# 05_LMS7002M_Misc.net
KiCad netlist of a schematic drawn in Altium Designer
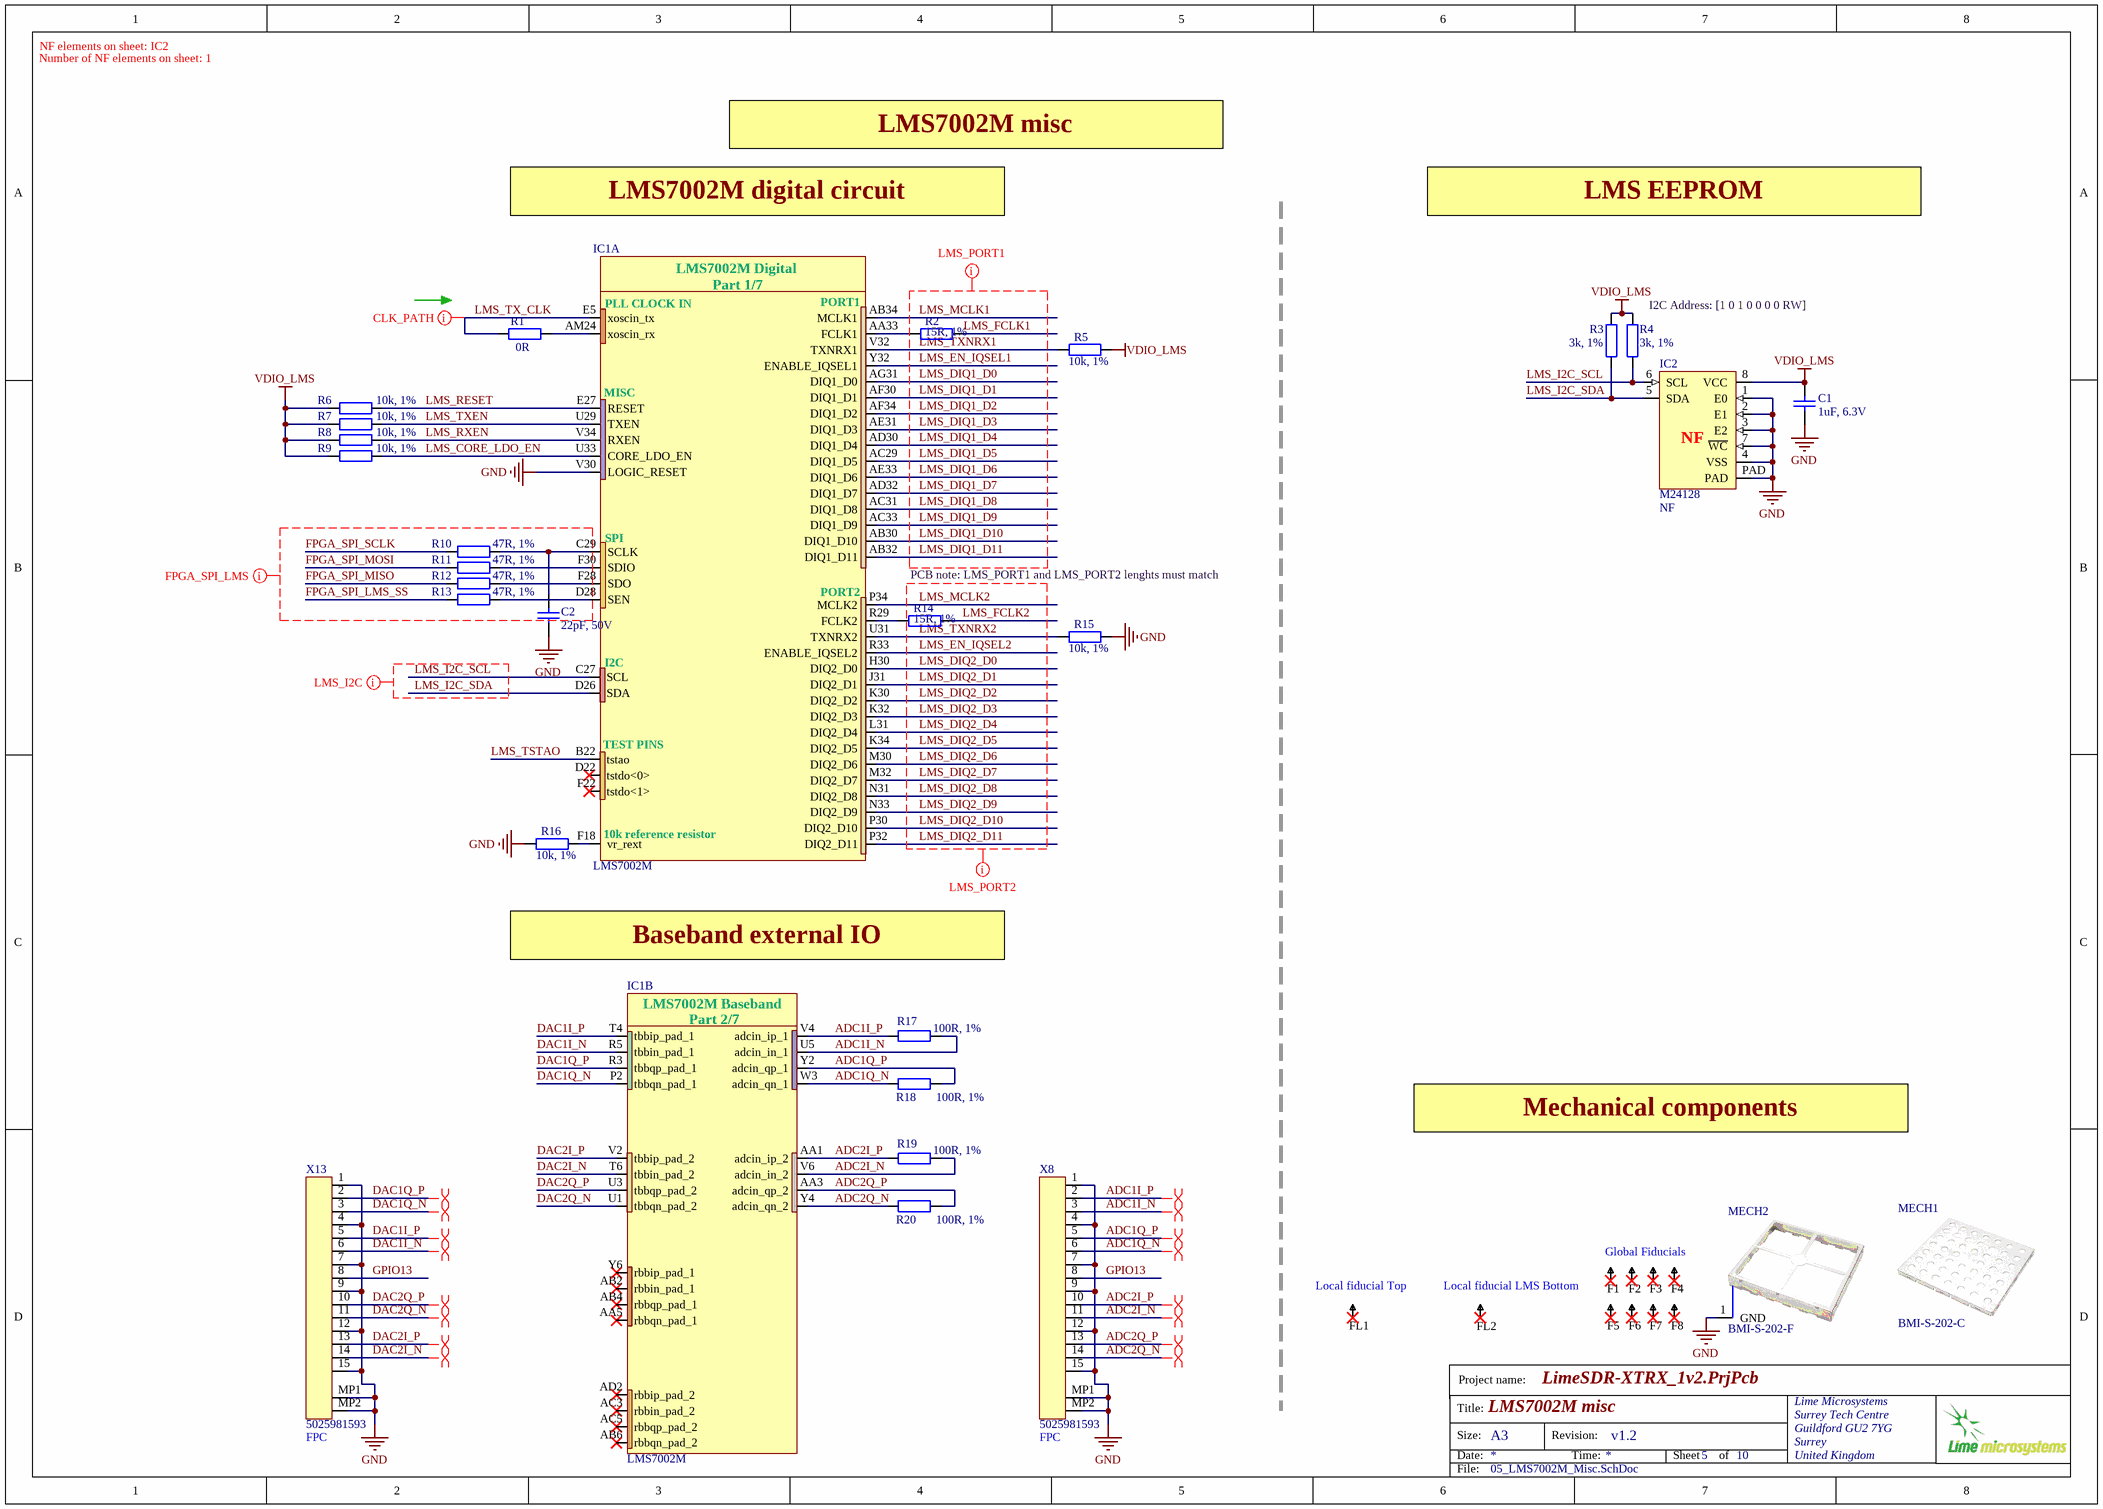
[diagram p0: 05_LMS7002M_Misc.SchDoc]

(export (version "E")
  (design (tool "Eeschema 10.0.6"))
  (components
    (comp (ref "C1")
      (value "1uF, 6.3V")
      (footprint "CAP0201")
      (fields (field (name "TOLERANCE") "±20%") (field (name "MANUFACTURER") "TDK Corporation"))
      (libsource (lib "LimeMicroAltiumLib_schLib") (part "Cap_0402"))
    )
    (comp (ref "C2")
      (value "22pF, 50V")
      (footprint "CAP0201")
      (fields
        (field (name "MANUFACTURER") "Murata")
        (field (name "TOLERANCE") "5%")
        (field (name "VOLTAGE") "50V")
      )
      (libsource (lib "LimeMicroAltiumLib_schLib") (part "Cap_0402"))
    )
    (comp (ref "F1")
      (value "Fiducial")
      (footprint "Fiducial")
      (libsource (lib "VGTU_Altium_lib") (part "Fiducial"))
    )
    (comp (ref "F2")
      (value "Fiducial")
      (footprint "Fiducial")
      (libsource (lib "VGTU_Altium_lib") (part "Fiducial"))
    )
    (comp (ref "F3")
      (value "Fiducial")
      (footprint "Fiducial")
      (libsource (lib "VGTU_Altium_lib") (part "Fiducial"))
    )
    (comp (ref "F4")
      (value "Fiducial")
      (footprint "Fiducial")
      (libsource (lib "VGTU_Altium_lib") (part "Fiducial"))
    )
    (comp (ref "F5")
      (value "Fiducial")
      (footprint "Fiducial")
      (libsource (lib "VGTU_Altium_lib") (part "Fiducial"))
    )
    (comp (ref "F6")
      (value "Fiducial")
      (footprint "Fiducial")
      (libsource (lib "VGTU_Altium_lib") (part "Fiducial"))
    )
    (comp (ref "F7")
      (value "Fiducial")
      (footprint "Fiducial")
      (libsource (lib "VGTU_Altium_lib") (part "Fiducial"))
    )
    (comp (ref "F8")
      (value "Fiducial")
      (footprint "Fiducial")
      (libsource (lib "VGTU_Altium_lib") (part "Fiducial"))
    )
    (comp (ref "FL1")
      (value "Fiducial")
      (footprint "Fiducial_local")
      (libsource (lib "") (part "Fiducial_1"))
    )
    (comp (ref "FL2")
      (value "Fiducial")
      (footprint "Fiducial_local")
      (libsource (lib "") (part "Fiducial_1"))
    )
    (comp (ref "IC1")
      (value "LMS7002M")
      (footprint "LMS7002M_v5_LESS_SILK")
      (description "Schematic symbol revision 4. Default footprint - 0.31mm pad")
      (fields (field (name "MANUFACTURER") "Lime Microsystems"))
      (libsource (lib "LimeMicroAltiumLib_schLib_r04") (part "LMS7002Mr4"))
    )
    (comp (ref "IC2")
      (value "M24128")
      (footprint "M24128-DFMC6TG")
      (fields (field (name "MANUFACTURER") "STMicroelectronics") (field (name "ASSEMBLY INFO") "NF"))
      (libsource (lib "LimeMicroAltiumLib_schLib") (part "M24128-DFMC6TG"))
    )
    (comp (ref "MECH1")
      (value "BMI-S-202-C")
      (footprint "BMI-S-202-C_RF_SHIELD_COVER")
      (fields (field (name "MANUFACTURER") "Laird"))
      (libsource (lib "LimeMicroAltiumLib_schLib_r04") (part "RFI_SHIELD_COVER_BMI-S-202-C"))
    )
    (comp (ref "MECH2")
      (value "BMI-S-202-F")
      (footprint "BMI-S-202-F_RF_SHIELD_FRAME_v3")
      (fields (field (name "MANUFACTURER") "Laird"))
      (libsource (lib "LimeMicroAltiumLib_schLib_r04") (part "RFI_SHIELD_FRAME_BMI-S-202-F"))
    )
    (comp (ref "R1")
      (value "0R")
      (footprint "RES0201")
      (fields (field (name "MANUFACTURER") "Yageo") (field (name "TOLERANCE") "5%"))
      (libsource (lib "LimeFPGAboard_schLib") (part "Res_0402"))
    )
    (comp (ref "R2")
      (value "15R, 1%")
      (footprint "RES0201")
      (fields (field (name "MANUFACTURER") "Yageo") (field (name "TOLERANCE") "1%"))
      (libsource (lib "LimeFPGAboard_schLib") (part "Res_0402"))
    )
    (comp (ref "R3")
      (value "3k, 1%")
      (footprint "RES0201")
      (fields (field (name "MANUFACTURER") "Yageo") (field (name "TOLERANCE") "1%"))
      (libsource (lib "LimeFPGAboard_schLib") (part "Res_0402"))
    )
    (comp (ref "R4")
      (value "3k, 1%")
      (footprint "RES0201")
      (fields (field (name "MANUFACTURER") "Yageo") (field (name "TOLERANCE") "1%"))
      (libsource (lib "LimeFPGAboard_schLib") (part "Res_0402"))
    )
    (comp (ref "R5")
      (value "10k, 1%")
      (footprint "RES0201")
      (fields (field (name "MANUFACTURER") "Yageo") (field (name "TOLERANCE") "1%"))
      (libsource (lib "LimeFPGAboard_schLib") (part "Res_0402"))
    )
    (comp (ref "R6")
      (value "10k, 1%")
      (footprint "RES0201")
      (fields (field (name "MANUFACTURER") "Yageo") (field (name "TOLERANCE") "1%"))
      (libsource (lib "LimeFPGAboard_schLib") (part "Res_0402"))
    )
    (comp (ref "R7")
      (value "10k, 1%")
      (footprint "RES0201")
      (fields (field (name "MANUFACTURER") "Yageo") (field (name "TOLERANCE") "1%"))
      (libsource (lib "LimeFPGAboard_schLib") (part "Res_0402"))
    )
    (comp (ref "R8")
      (value "10k, 1%")
      (footprint "RES0201")
      (fields (field (name "MANUFACTURER") "Yageo") (field (name "TOLERANCE") "1%"))
      (libsource (lib "LimeFPGAboard_schLib") (part "Res_0402"))
    )
    (comp (ref "R9")
      (value "10k, 1%")
      (footprint "RES0201")
      (fields (field (name "MANUFACTURER") "Yageo") (field (name "TOLERANCE") "1%"))
      (libsource (lib "LimeFPGAboard_schLib") (part "Res_0402"))
    )
    (comp (ref "R10")
      (value "47R, 1%")
      (footprint "RES0201")
      (fields (field (name "MANUFACTURER") "Yageo") (field (name "TOLERANCE") "1%"))
      (libsource (lib "LimeFPGAboard_schLib") (part "Res_0402"))
    )
    (comp (ref "R11")
      (value "47R, 1%")
      (footprint "RES0201")
      (fields (field (name "MANUFACTURER") "Yageo") (field (name "TOLERANCE") "1%"))
      (libsource (lib "LimeFPGAboard_schLib") (part "Res_0402"))
    )
    (comp (ref "R12")
      (value "47R, 1%")
      (footprint "RES0201")
      (fields (field (name "MANUFACTURER") "Yageo") (field (name "TOLERANCE") "1%"))
      (libsource (lib "LimeFPGAboard_schLib") (part "Res_0402"))
    )
    (comp (ref "R13")
      (value "47R, 1%")
      (footprint "RES0201")
      (fields (field (name "MANUFACTURER") "Yageo") (field (name "TOLERANCE") "1%"))
      (libsource (lib "LimeFPGAboard_schLib") (part "Res_0402"))
    )
    (comp (ref "R14")
      (value "15R, 1%")
      (footprint "RES0201")
      (fields (field (name "MANUFACTURER") "Yageo") (field (name "TOLERANCE") "1%"))
      (libsource (lib "LimeFPGAboard_schLib") (part "Res_0402"))
    )
    (comp (ref "R15")
      (value "10k, 1%")
      (footprint "RES0201")
      (fields (field (name "MANUFACTURER") "Yageo") (field (name "TOLERANCE") "1%"))
      (libsource (lib "LimeFPGAboard_schLib") (part "Res_0402"))
    )
    (comp (ref "R16")
      (value "10k, 1%")
      (footprint "RES0201")
      (fields (field (name "MANUFACTURER") "Yageo") (field (name "TOLERANCE") "1%"))
      (libsource (lib "LimeFPGAboard_schLib") (part "Res_0402"))
    )
    (comp (ref "R17")
      (value "100R, 1%")
      (footprint "RES0201")
      (fields (field (name "MANUFACTURER") "Yageo") (field (name "TOLERANCE") "1%"))
      (libsource (lib "LimeFPGAboard_schLib") (part "Res_0402"))
    )
    (comp (ref "R18")
      (value "100R, 1%")
      (footprint "RES0201")
      (fields (field (name "MANUFACTURER") "Yageo") (field (name "TOLERANCE") "1%"))
      (libsource (lib "LimeFPGAboard_schLib") (part "Res_0402"))
    )
    (comp (ref "R19")
      (value "100R, 1%")
      (footprint "RES0201")
      (fields (field (name "MANUFACTURER") "Yageo") (field (name "TOLERANCE") "1%"))
      (libsource (lib "LimeFPGAboard_schLib") (part "Res_0402"))
    )
    (comp (ref "R20")
      (value "100R, 1%")
      (footprint "RES0201")
      (fields (field (name "MANUFACTURER") "Yageo") (field (name "TOLERANCE") "1%"))
      (libsource (lib "LimeFPGAboard_schLib") (part "Res_0402"))
    )
    (comp (ref "X8")
      (value "5025981593")
      (footprint "5025981593_FPC_connector")
      (fields (field (name "MANUFACTURER") "Molex"))
      (libsource (lib "LimeMicroAltiumLib_schLib_r04") (part "5025981593_FPC_connector"))
    )
    (comp (ref "X13")
      (value "5025981593")
      (footprint "5025981593_FPC_connector")
      (fields (field (name "MANUFACTURER") "Molex"))
      (libsource (lib "LimeMicroAltiumLib_schLib_r04") (part "5025981593_FPC_connector"))
    )
  )
  (nets
    (net (code "1") (name "/ADC1I_N") (class "Default")
      (node (ref "IC1") (pin "U5") (pinfunction "adcin_in_1_U5") (pintype "passive"))
      (node (ref "R17") (pin "2") (pinfunction "2_2") (pintype "passive"))
      (node (ref "X8") (pin "3") (pinfunction "3_3") (pintype "passive"))
    )
    (net (code "2") (name "/ADC1I_P") (class "Default")
      (node (ref "IC1") (pin "V4") (pinfunction "adcin_ip_1_V4") (pintype "passive"))
      (node (ref "R17") (pin "1") (pinfunction "1_1") (pintype "passive"))
      (node (ref "X8") (pin "2") (pinfunction "2_2") (pintype "passive"))
    )
    (net (code "3") (name "/ADC1Q_N") (class "Default")
      (node (ref "IC1") (pin "W3") (pinfunction "adcin_qn_1_W3") (pintype "passive"))
      (node (ref "R18") (pin "1") (pinfunction "1_1") (pintype "passive"))
      (node (ref "X8") (pin "6") (pinfunction "6_6") (pintype "passive"))
    )
    (net (code "4") (name "/ADC1Q_P") (class "Default")
      (node (ref "IC1") (pin "Y2") (pinfunction "adcin_qp_1_Y2") (pintype "passive"))
      (node (ref "R18") (pin "2") (pinfunction "2_2") (pintype "passive"))
      (node (ref "X8") (pin "5") (pinfunction "5_5") (pintype "passive"))
    )
    (net (code "5") (name "/ADC2I_N") (class "Default")
      (node (ref "IC1") (pin "V6") (pinfunction "adcin_in_2_V6") (pintype "passive"))
      (node (ref "R19") (pin "2") (pinfunction "2_2") (pintype "passive"))
      (node (ref "X8") (pin "11") (pinfunction "11_11") (pintype "passive"))
    )
    (net (code "6") (name "/ADC2I_P") (class "Default")
      (node (ref "IC1") (pin "AA1") (pinfunction "adcin_ip_2_AA1") (pintype "passive"))
      (node (ref "R19") (pin "1") (pinfunction "1_1") (pintype "passive"))
      (node (ref "X8") (pin "10") (pinfunction "10_10") (pintype "passive"))
    )
    (net (code "7") (name "/ADC2Q_N") (class "Default")
      (node (ref "IC1") (pin "Y4") (pinfunction "adcin_qn_2_Y4") (pintype "passive"))
      (node (ref "R20") (pin "1") (pinfunction "1_1") (pintype "passive"))
      (node (ref "X8") (pin "14") (pinfunction "14_14") (pintype "passive"))
    )
    (net (code "8") (name "/ADC2Q_P") (class "Default")
      (node (ref "IC1") (pin "AA3") (pinfunction "adcin_qp_2_AA3") (pintype "passive"))
      (node (ref "R20") (pin "2") (pinfunction "2_2") (pintype "passive"))
      (node (ref "X8") (pin "13") (pinfunction "13_13") (pintype "passive"))
    )
    (net (code "9") (name "/DAC1I_N") (class "Default")
      (node (ref "IC1") (pin "R5") (pinfunction "tbbin_pad_1_R5") (pintype "passive"))
      (node (ref "X13") (pin "6") (pinfunction "6_6") (pintype "passive"))
    )
    (net (code "10") (name "/DAC1I_P") (class "Default")
      (node (ref "IC1") (pin "T4") (pinfunction "tbbip_pad_1_T4") (pintype "passive"))
      (node (ref "X13") (pin "5") (pinfunction "5_5") (pintype "passive"))
    )
    (net (code "11") (name "/DAC1Q_N") (class "Default")
      (node (ref "IC1") (pin "P2") (pinfunction "tbbqn_pad_1_P2") (pintype "passive"))
      (node (ref "X13") (pin "3") (pinfunction "3_3") (pintype "passive"))
    )
    (net (code "12") (name "/DAC1Q_P") (class "Default")
      (node (ref "IC1") (pin "R3") (pinfunction "tbbqp_pad_1_R3") (pintype "passive"))
      (node (ref "X13") (pin "2") (pinfunction "2_2") (pintype "passive"))
    )
    (net (code "13") (name "/DAC2I_N") (class "Default")
      (node (ref "IC1") (pin "T6") (pinfunction "tbbin_pad_2_T6") (pintype "passive"))
      (node (ref "X13") (pin "14") (pinfunction "14_14") (pintype "passive"))
    )
    (net (code "14") (name "/DAC2I_P") (class "Default")
      (node (ref "IC1") (pin "V2") (pinfunction "tbbip_pad_2_V2") (pintype "passive"))
      (node (ref "X13") (pin "13") (pinfunction "13_13") (pintype "passive"))
    )
    (net (code "15") (name "/DAC2Q_N") (class "Default")
      (node (ref "IC1") (pin "U1") (pinfunction "tbbqn_pad_2_U1") (pintype "passive"))
      (node (ref "X13") (pin "11") (pinfunction "11_11") (pintype "passive"))
    )
    (net (code "16") (name "/DAC2Q_P") (class "Default")
      (node (ref "IC1") (pin "U3") (pinfunction "tbbqp_pad_2_U3") (pintype "passive"))
      (node (ref "X13") (pin "10") (pinfunction "10_10") (pintype "passive"))
    )
    (net (code "17") (name "/FPGA_SPI_LMS_SS") (class "Default")
      (node (ref "R13") (pin "2") (pinfunction "2_2") (pintype "passive"))
    )
    (net (code "18") (name "/FPGA_SPI_MISO") (class "Default")
      (node (ref "R12") (pin "2") (pinfunction "2_2") (pintype "passive"))
    )
    (net (code "19") (name "/FPGA_SPI_MOSI") (class "Default")
      (node (ref "R11") (pin "2") (pinfunction "2_2") (pintype "passive"))
    )
    (net (code "20") (name "/FPGA_SPI_SCLK") (class "Default")
      (node (ref "R10") (pin "2") (pinfunction "2_2") (pintype "passive"))
    )
    (net (code "21") (name "/GPIO13") (class "Default")
      (node (ref "X13") (pin "8") (pinfunction "8_8") (pintype "passive"))
      (node (ref "X8") (pin "8") (pinfunction "8_8") (pintype "passive"))
    )
    (net (code "22") (name "/LMS_CORE_LDO_EN") (class "Default")
      (node (ref "IC1") (pin "U33") (pinfunction "CORE_LDO_EN_U33") (pintype "passive"))
      (node (ref "R9") (pin "1") (pinfunction "1_1") (pintype "passive"))
    )
    (net (code "23") (name "/LMS_DIQ1_D0") (class "Default")
      (node (ref "IC1") (pin "AG31") (pinfunction "DIQ1_D0_AG31") (pintype "passive"))
    )
    (net (code "24") (name "/LMS_DIQ1_D1") (class "Default")
      (node (ref "IC1") (pin "AF30") (pinfunction "DIQ1_D1_AF30") (pintype "passive"))
    )
    (net (code "25") (name "/LMS_DIQ1_D2") (class "Default")
      (node (ref "IC1") (pin "AF34") (pinfunction "DIQ1_D2_AF34") (pintype "passive"))
    )
    (net (code "26") (name "/LMS_DIQ1_D3") (class "Default")
      (node (ref "IC1") (pin "AE31") (pinfunction "DIQ1_D3_AE31") (pintype "passive"))
    )
    (net (code "27") (name "/LMS_DIQ1_D4") (class "Default")
      (node (ref "IC1") (pin "AD30") (pinfunction "DIQ1_D4_AD30") (pintype "passive"))
    )
    (net (code "28") (name "/LMS_DIQ1_D5") (class "Default")
      (node (ref "IC1") (pin "AC29") (pinfunction "DIQ1_D5_AC29") (pintype "passive"))
    )
    (net (code "29") (name "/LMS_DIQ1_D6") (class "Default")
      (node (ref "IC1") (pin "AE33") (pinfunction "DIQ1_D6_AE33") (pintype "passive"))
    )
    (net (code "30") (name "/LMS_DIQ1_D7") (class "Default")
      (node (ref "IC1") (pin "AD32") (pinfunction "DIQ1_D7_AD32") (pintype "passive"))
    )
    (net (code "31") (name "/LMS_DIQ1_D8") (class "Default")
      (node (ref "IC1") (pin "AC31") (pinfunction "DIQ1_D8_AC31") (pintype "passive"))
    )
    (net (code "32") (name "/LMS_DIQ1_D9") (class "Default")
      (node (ref "IC1") (pin "AC33") (pinfunction "DIQ1_D9_AC33") (pintype "passive"))
    )
    (net (code "33") (name "/LMS_DIQ1_D10") (class "Default")
      (node (ref "IC1") (pin "AB30") (pinfunction "DIQ1_D10_AB30") (pintype "passive"))
    )
    (net (code "34") (name "/LMS_DIQ1_D11") (class "Default")
      (node (ref "IC1") (pin "AB32") (pinfunction "DIQ1_D11_AB32") (pintype "passive"))
    )
    (net (code "35") (name "/LMS_DIQ2_D0") (class "Default")
      (node (ref "IC1") (pin "H30") (pinfunction "DIQ2_D0_H30") (pintype "passive"))
    )
    (net (code "36") (name "/LMS_DIQ2_D1") (class "Default")
      (node (ref "IC1") (pin "J31") (pinfunction "DIQ2_D1_J31") (pintype "passive"))
    )
    (net (code "37") (name "/LMS_DIQ2_D2") (class "Default")
      (node (ref "IC1") (pin "K30") (pinfunction "DIQ2_D2_K30") (pintype "passive"))
    )
    (net (code "38") (name "/LMS_DIQ2_D3") (class "Default")
      (node (ref "IC1") (pin "K32") (pinfunction "DIQ2_D3_K32") (pintype "passive"))
    )
    (net (code "39") (name "/LMS_DIQ2_D4") (class "Default")
      (node (ref "IC1") (pin "L31") (pinfunction "DIQ2_D4_L31") (pintype "passive"))
    )
    (net (code "40") (name "/LMS_DIQ2_D5") (class "Default")
      (node (ref "IC1") (pin "K34") (pinfunction "DIQ2_D5_K34") (pintype "passive"))
    )
    (net (code "41") (name "/LMS_DIQ2_D6") (class "Default")
      (node (ref "IC1") (pin "M30") (pinfunction "DIQ2_D6_M30") (pintype "passive"))
    )
    (net (code "42") (name "/LMS_DIQ2_D7") (class "Default")
      (node (ref "IC1") (pin "M32") (pinfunction "DIQ2_D7_M32") (pintype "passive"))
    )
    (net (code "43") (name "/LMS_DIQ2_D8") (class "Default")
      (node (ref "IC1") (pin "N31") (pinfunction "DIQ2_D8_N31") (pintype "passive"))
    )
    (net (code "44") (name "/LMS_DIQ2_D9") (class "Default")
      (node (ref "IC1") (pin "N33") (pinfunction "DIQ2_D9_N33") (pintype "passive"))
    )
    (net (code "45") (name "/LMS_DIQ2_D10") (class "Default")
      (node (ref "IC1") (pin "P30") (pinfunction "DIQ2_D10_P30") (pintype "passive"))
    )
    (net (code "46") (name "/LMS_DIQ2_D11") (class "Default")
      (node (ref "IC1") (pin "P32") (pinfunction "DIQ2_D11_P32") (pintype "passive"))
    )
    (net (code "47") (name "/LMS_EN_IQSEL1") (class "Default")
      (node (ref "IC1") (pin "Y32") (pinfunction "ENABLE_IQSEL1_Y32") (pintype "passive"))
    )
    (net (code "48") (name "/LMS_EN_IQSEL2") (class "Default")
      (node (ref "IC1") (pin "R33") (pinfunction "ENABLE_IQSEL2_R33") (pintype "passive"))
    )
    (net (code "49") (name "/LMS_FCLK1") (class "Default")
      (node (ref "R2") (pin "1") (pinfunction "1_1") (pintype "passive"))
    )
    (net (code "50") (name "/LMS_FCLK2") (class "Default")
      (node (ref "R14") (pin "1") (pinfunction "1_1") (pintype "passive"))
    )
    (net (code "51") (name "/LMS_I2C_SCL") (class "Default")
      (node (ref "IC1") (pin "C27") (pinfunction "SCL_C27") (pintype "passive"))
      (node (ref "IC2") (pin "6") (pinfunction "SCL_6") (pintype "input"))
      (node (ref "R4") (pin "1") (pinfunction "1_1") (pintype "passive"))
    )
    (net (code "52") (name "/LMS_I2C_SDA") (class "Default")
      (node (ref "IC1") (pin "D26") (pinfunction "SDA_D26") (pintype "passive"))
      (node (ref "IC2") (pin "5") (pinfunction "SDA_5") (pintype "bidirectional"))
      (node (ref "R3") (pin "1") (pinfunction "1_1") (pintype "passive"))
    )
    (net (code "53") (name "/LMS_MCLK1") (class "Default")
      (node (ref "IC1") (pin "AB34") (pinfunction "MCLK1_AB34") (pintype "passive"))
    )
    (net (code "54") (name "/LMS_MCLK2") (class "Default")
      (node (ref "IC1") (pin "P34") (pinfunction "MCLK2_P34") (pintype "passive"))
    )
    (net (code "55") (name "/LMS_RESET") (class "Default")
      (node (ref "IC1") (pin "E27") (pinfunction "RESET_E27") (pintype "passive"))
      (node (ref "R6") (pin "1") (pinfunction "1_1") (pintype "passive"))
    )
    (net (code "56") (name "/LMS_RXEN") (class "Default")
      (node (ref "IC1") (pin "V34") (pinfunction "RXEN_V34") (pintype "passive"))
      (node (ref "R8") (pin "1") (pinfunction "1_1") (pintype "passive"))
    )
    (net (code "57") (name "/LMS_TSTAO") (class "Default")
      (node (ref "IC1") (pin "B22") (pinfunction "tstao_B22") (pintype "passive"))
    )
    (net (code "58") (name "/LMS_TXEN") (class "Default")
      (node (ref "IC1") (pin "U29") (pinfunction "TXEN_U29") (pintype "passive"))
      (node (ref "R7") (pin "1") (pinfunction "1_1") (pintype "passive"))
    )
    (net (code "59") (name "/LMS_TXNRX1") (class "Default")
      (node (ref "IC1") (pin "V32") (pinfunction "TXNRX1_V32") (pintype "passive"))
      (node (ref "R5") (pin "2") (pinfunction "2_2") (pintype "passive"))
    )
    (net (code "60") (name "/LMS_TXNRX2") (class "Default")
      (node (ref "IC1") (pin "U31") (pinfunction "TXNRX2_U31") (pintype "passive"))
      (node (ref "R15") (pin "2") (pinfunction "2_2") (pintype "passive"))
    )
    (net (code "61") (name "/LMS_TX_CLK") (class "Default")
      (node (ref "IC1") (pin "E5") (pinfunction "xoscin_tx_E5") (pintype "passive"))
      (node (ref "R1") (pin "1") (pinfunction "1_1") (pintype "passive"))
    )
    (net (code "62") (name "GND") (class "Default")
      (node (ref "C1") (pin "2") (pinfunction "2_2") (pintype "passive"))
      (node (ref "C2") (pin "1") (pinfunction "1_1") (pintype "passive"))
      (node (ref "IC1") (pin "V30") (pinfunction "LOGIC_RESET_V30") (pintype "passive"))
      (node (ref "IC2") (pin "1") (pinfunction "E0_1") (pintype "input"))
      (node (ref "IC2") (pin "2") (pinfunction "E1_2") (pintype "input"))
      (node (ref "IC2") (pin "3") (pinfunction "E2_3") (pintype "input"))
      (node (ref "IC2") (pin "4") (pinfunction "VSS_4") (pintype "power_in"))
      (node (ref "IC2") (pin "7") (pinfunction "~{WC}_7") (pintype "input"))
      (node (ref "IC2") (pin "PAD") (pinfunction "PAD_PAD") (pintype "power_in"))
      (node (ref "MECH2") (pin "1") (pinfunction "GND_1") (pintype "passive"))
      (node (ref "R15") (pin "1") (pinfunction "1_1") (pintype "passive"))
      (node (ref "R16") (pin "2") (pinfunction "2_2") (pintype "passive"))
      (node (ref "X13") (pin "1") (pinfunction "1_1") (pintype "passive"))
      (node (ref "X13") (pin "12") (pinfunction "12_12") (pintype "passive"))
      (node (ref "X13") (pin "15") (pinfunction "15_15") (pintype "passive"))
      (node (ref "X13") (pin "4") (pinfunction "4_4") (pintype "passive"))
      (node (ref "X13") (pin "7") (pinfunction "7_7") (pintype "passive"))
      (node (ref "X13") (pin "9") (pinfunction "9_9") (pintype "passive"))
      (node (ref "X13") (pin "MP1") (pinfunction "MP1_MP1") (pintype "passive"))
      (node (ref "X13") (pin "MP2") (pinfunction "MP2_MP2") (pintype "passive"))
      (node (ref "X8") (pin "1") (pinfunction "1_1") (pintype "passive"))
      (node (ref "X8") (pin "12") (pinfunction "12_12") (pintype "passive"))
      (node (ref "X8") (pin "15") (pinfunction "15_15") (pintype "passive"))
      (node (ref "X8") (pin "4") (pinfunction "4_4") (pintype "passive"))
      (node (ref "X8") (pin "7") (pinfunction "7_7") (pintype "passive"))
      (node (ref "X8") (pin "9") (pinfunction "9_9") (pintype "passive"))
      (node (ref "X8") (pin "MP1") (pinfunction "MP1_MP1") (pintype "passive"))
      (node (ref "X8") (pin "MP2") (pinfunction "MP2_MP2") (pintype "passive"))
    )
    (net (code "63") (name "Net-(IC1A-FCLK1)") (class "Default")
      (node (ref "IC1") (pin "AA33") (pinfunction "FCLK1_AA33") (pintype "passive"))
      (node (ref "R2") (pin "2") (pinfunction "2_2") (pintype "passive"))
    )
    (net (code "64") (name "Net-(IC1A-FCLK2)") (class "Default")
      (node (ref "IC1") (pin "R29") (pinfunction "FCLK2_R29") (pintype "passive"))
      (node (ref "R14") (pin "2") (pinfunction "2_2") (pintype "passive"))
    )
    (net (code "65") (name "Net-(IC1A-SCLK)") (class "Default")
      (node (ref "C2") (pin "2") (pinfunction "2_2") (pintype "passive"))
      (node (ref "IC1") (pin "C29") (pinfunction "SCLK_C29") (pintype "passive"))
      (node (ref "R10") (pin "1") (pinfunction "1_1") (pintype "passive"))
    )
    (net (code "66") (name "Net-(IC1A-SDIO)") (class "Default")
      (node (ref "IC1") (pin "F30") (pinfunction "SDIO_F30") (pintype "passive"))
      (node (ref "R11") (pin "1") (pinfunction "1_1") (pintype "passive"))
    )
    (net (code "67") (name "Net-(IC1A-SDO)") (class "Default")
      (node (ref "IC1") (pin "F28") (pinfunction "SDO_F28") (pintype "passive"))
      (node (ref "R12") (pin "1") (pinfunction "1_1") (pintype "passive"))
    )
    (net (code "68") (name "Net-(IC1A-SEN)") (class "Default")
      (node (ref "IC1") (pin "D28") (pinfunction "SEN_D28") (pintype "passive"))
      (node (ref "R13") (pin "1") (pinfunction "1_1") (pintype "passive"))
    )
    (net (code "69") (name "Net-(IC1A-vr_rext)") (class "Default")
      (node (ref "IC1") (pin "F18") (pinfunction "vr_rext_F18") (pintype "passive"))
      (node (ref "R16") (pin "1") (pinfunction "1_1") (pintype "passive"))
    )
    (net (code "70") (name "Net-(IC1A-xoscin_rx)") (class "Default")
      (node (ref "IC1") (pin "AM24") (pinfunction "xoscin_rx_AM24") (pintype "passive"))
      (node (ref "R1") (pin "2") (pinfunction "2_2") (pintype "passive"))
    )
    (net (code "71") (name "VDIO_LMS") (class "Default")
      (node (ref "C1") (pin "1") (pinfunction "1_1") (pintype "passive"))
      (node (ref "IC2") (pin "8") (pinfunction "VCC_8") (pintype "power_in"))
      (node (ref "R3") (pin "2") (pinfunction "2_2") (pintype "passive"))
      (node (ref "R4") (pin "2") (pinfunction "2_2") (pintype "passive"))
      (node (ref "R5") (pin "1") (pinfunction "1_1") (pintype "passive"))
      (node (ref "R6") (pin "2") (pinfunction "2_2") (pintype "passive"))
      (node (ref "R7") (pin "2") (pinfunction "2_2") (pintype "passive"))
      (node (ref "R8") (pin "2") (pinfunction "2_2") (pintype "passive"))
      (node (ref "R9") (pin "2") (pinfunction "2_2") (pintype "passive"))
    )
    (net (code "72") (name "unconnected-(F1-Pad1)") (class "Default")
      (node (ref "F1") (pin "1") (pintype "passive+no_connect"))
    )
    (net (code "73") (name "unconnected-(F2-Pad1)") (class "Default")
      (node (ref "F2") (pin "1") (pintype "passive+no_connect"))
    )
    (net (code "74") (name "unconnected-(F3-Pad1)") (class "Default")
      (node (ref "F3") (pin "1") (pintype "passive+no_connect"))
    )
    (net (code "75") (name "unconnected-(F4-Pad1)") (class "Default")
      (node (ref "F4") (pin "1") (pintype "passive+no_connect"))
    )
    (net (code "76") (name "unconnected-(F5-Pad1)") (class "Default")
      (node (ref "F5") (pin "1") (pintype "passive+no_connect"))
    )
    (net (code "77") (name "unconnected-(F6-Pad1)") (class "Default")
      (node (ref "F6") (pin "1") (pintype "passive+no_connect"))
    )
    (net (code "78") (name "unconnected-(F7-Pad1)") (class "Default")
      (node (ref "F7") (pin "1") (pintype "passive+no_connect"))
    )
    (net (code "79") (name "unconnected-(F8-Pad1)") (class "Default")
      (node (ref "F8") (pin "1") (pintype "passive+no_connect"))
    )
    (net (code "80") (name "unconnected-(FL1-Pad1)") (class "Default")
      (node (ref "FL1") (pin "1") (pintype "passive+no_connect"))
    )
    (net (code "81") (name "unconnected-(FL2-Pad1)") (class "Default")
      (node (ref "FL2") (pin "1") (pintype "passive+no_connect"))
    )
    (net (code "82") (name "unconnected-(IC1A-tstdo<0>-PadD22)") (class "Default")
      (node (ref "IC1") (pin "D22") (pinfunction "tstdo<0>_D22") (pintype "passive+no_connect"))
    )
    (net (code "83") (name "unconnected-(IC1A-tstdo<1>-PadF22)") (class "Default")
      (node (ref "IC1") (pin "F22") (pinfunction "tstdo<1>_F22") (pintype "passive+no_connect"))
    )
    (net (code "84") (name "unconnected-(IC1B-rbbin_pad_1-PadAB2)") (class "Default")
      (node (ref "IC1") (pin "AB2") (pinfunction "rbbin_pad_1_AB2") (pintype "passive+no_connect"))
    )
    (net (code "85") (name "unconnected-(IC1B-rbbin_pad_2-PadAC3)") (class "Default")
      (node (ref "IC1") (pin "AC3") (pinfunction "rbbin_pad_2_AC3") (pintype "passive+no_connect"))
    )
    (net (code "86") (name "unconnected-(IC1B-rbbip_pad_1-PadY6)") (class "Default")
      (node (ref "IC1") (pin "Y6") (pinfunction "rbbip_pad_1_Y6") (pintype "passive+no_connect"))
    )
    (net (code "87") (name "unconnected-(IC1B-rbbip_pad_2-PadAD2)") (class "Default")
      (node (ref "IC1") (pin "AD2") (pinfunction "rbbip_pad_2_AD2") (pintype "passive+no_connect"))
    )
    (net (code "88") (name "unconnected-(IC1B-rbbqn_pad_1-PadAA5)") (class "Default")
      (node (ref "IC1") (pin "AA5") (pinfunction "rbbqn_pad_1_AA5") (pintype "passive+no_connect"))
    )
    (net (code "89") (name "unconnected-(IC1B-rbbqn_pad_2-PadAB6)") (class "Default")
      (node (ref "IC1") (pin "AB6") (pinfunction "rbbqn_pad_2_AB6") (pintype "passive+no_connect"))
    )
    (net (code "90") (name "unconnected-(IC1B-rbbqp_pad_1-PadAB4)") (class "Default")
      (node (ref "IC1") (pin "AB4") (pinfunction "rbbqp_pad_1_AB4") (pintype "passive+no_connect"))
    )
    (net (code "91") (name "unconnected-(IC1B-rbbqp_pad_2-PadAC5)") (class "Default")
      (node (ref "IC1") (pin "AC5") (pinfunction "rbbqp_pad_2_AC5") (pintype "passive+no_connect"))
    )
  )
)
